# ZMBo_Main.net
KiCad netlist of a schematic drawn in Altium Designer
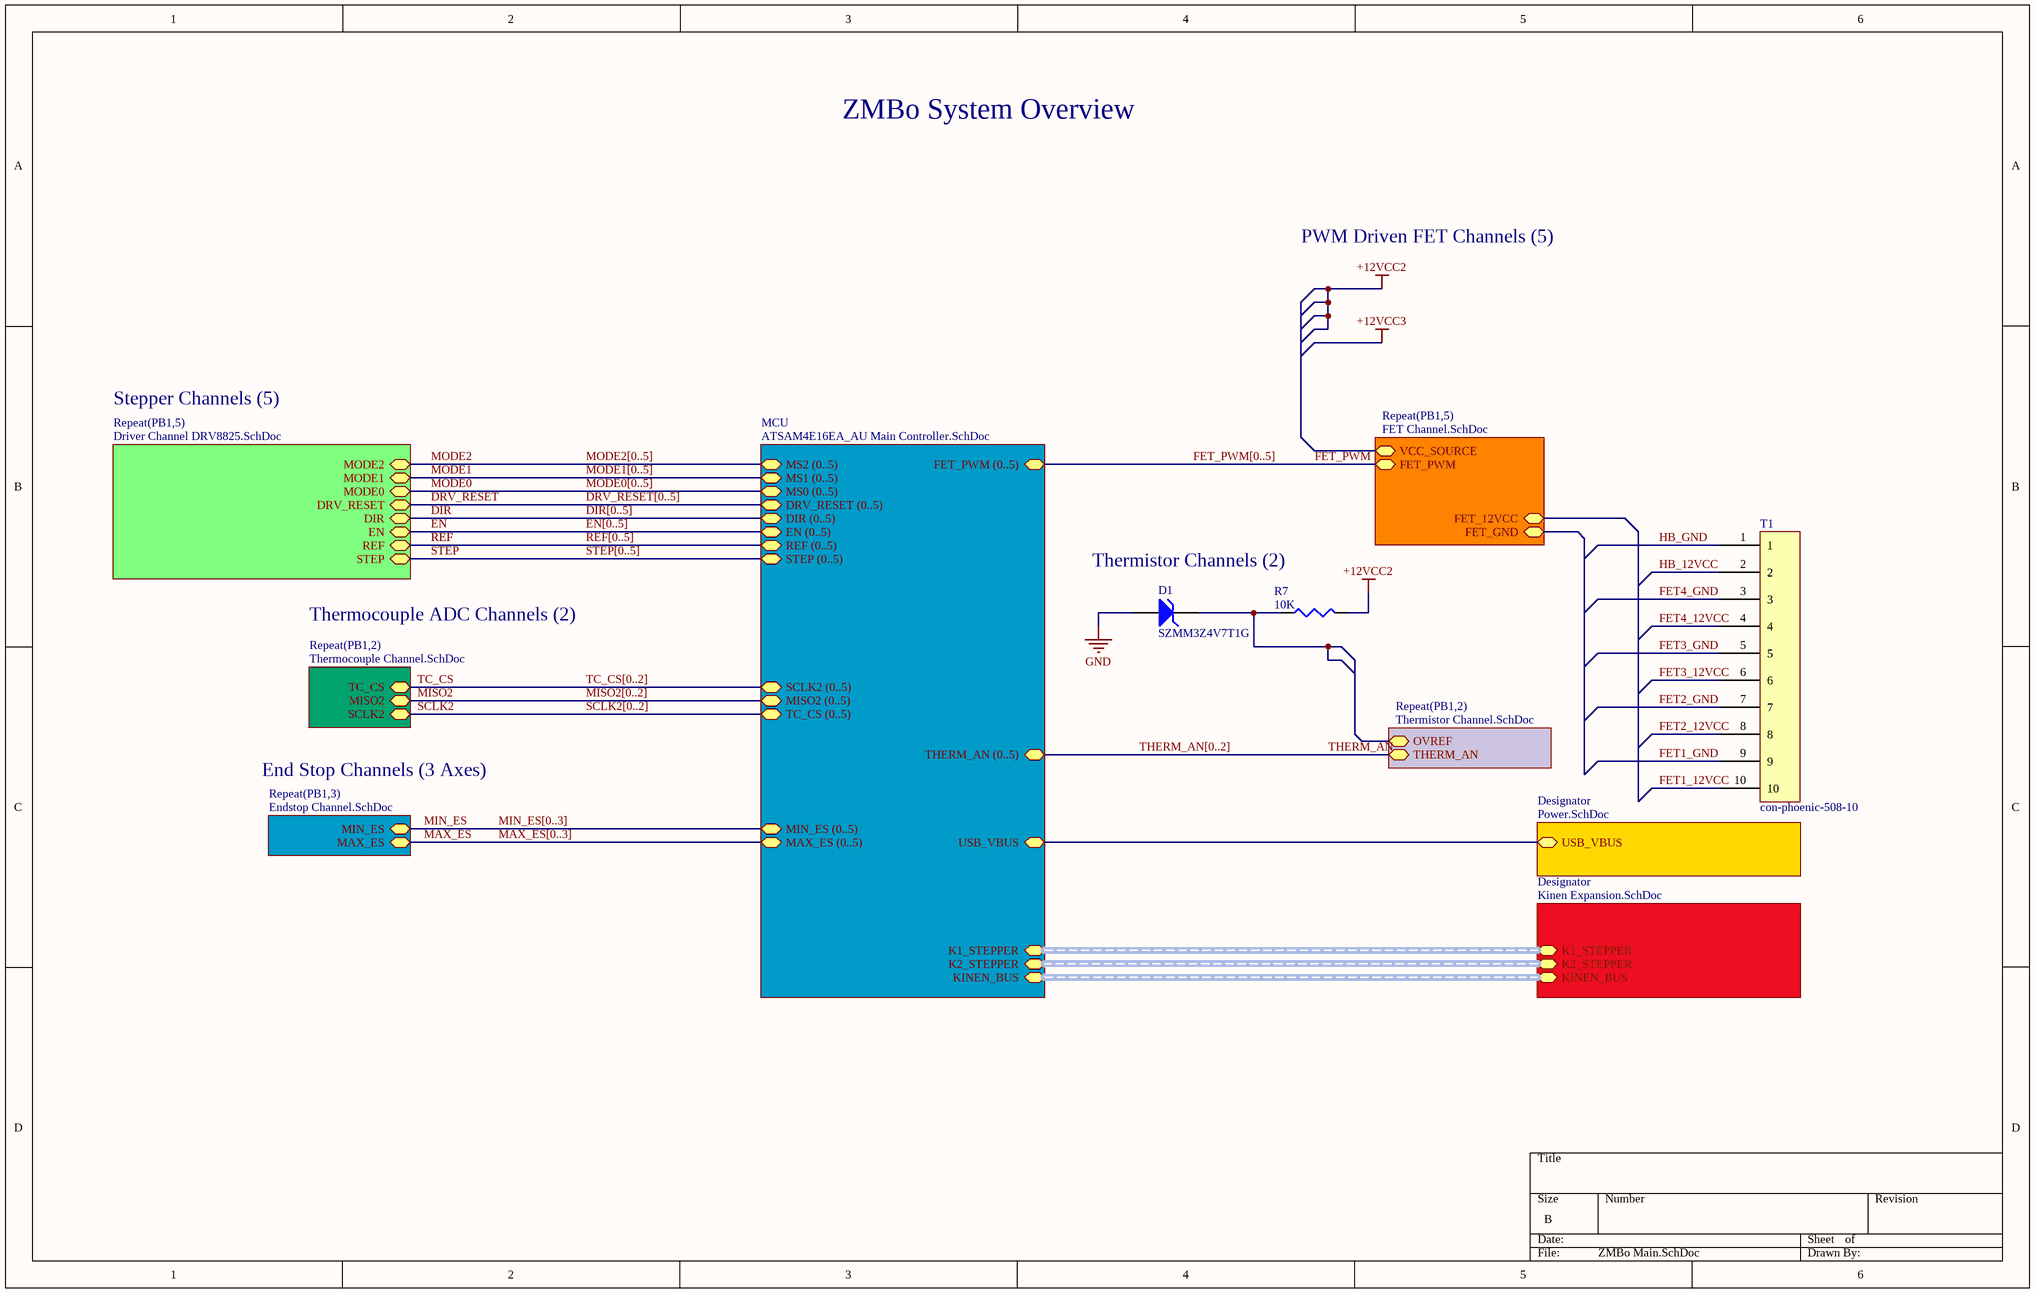
[diagram p0: ZMBo Main.SchDoc]

(export (version "E")
  (design (tool "Eeschema 10.0.6"))
  (components
    (comp (ref "D1")
      (value "SZMM3Z4V7T1G")
      (footprint "SZMM3Z4V7T1G")
      (description "Zener Diode")
      (fields (field (name "PUBLISHER") "Altium Limited"))
      (libsource (lib "Miscellaneous Devices") (part "D Zener"))
    )
    (comp (ref "R7")
      (value "10K")
      (footprint "J1-0603")
      (description "Resistor")
      (fields (field (name "Comment") "Res3") (field (name "PUBLISHER") "Altium Limited"))
      (libsource (lib "Miscellaneous Devices") (part "Res3"))
    )
    (comp (ref "T1")
      (value "con-phoenic-508-10")
      (footprint "con-phoenix-508 - 10")
      (libsource (lib "ZMBo Schematic Library") (part "con-phoenic-508-10"))
    )
  )
  (nets
    (net (code "75") (name "+12VCC2") (class "Default")
      (node (ref "R7") (pin "2") (pinfunction "2_2") (pintype "passive"))
    )
    (net (code "83") (name "/FET1_12VCC") (class "Default")
      (node (ref "T1") (pin "10") (pinfunction "10_10") (pintype "passive"))
    )
    (net (code "84") (name "/FET1_GND") (class "Default")
      (node (ref "T1") (pin "9") (pinfunction "9_9") (pintype "passive"))
    )
    (net (code "85") (name "/FET2_12VCC") (class "Default")
      (node (ref "T1") (pin "8") (pinfunction "8_8") (pintype "passive"))
    )
    (net (code "86") (name "/FET2_GND") (class "Default")
      (node (ref "T1") (pin "7") (pinfunction "7_7") (pintype "passive"))
    )
    (net (code "87") (name "/FET3_12VCC") (class "Default")
      (node (ref "T1") (pin "6") (pinfunction "6_6") (pintype "passive"))
    )
    (net (code "88") (name "/FET3_GND") (class "Default")
      (node (ref "T1") (pin "5") (pinfunction "5_5") (pintype "passive"))
    )
    (net (code "89") (name "/FET4_12VCC") (class "Default")
      (node (ref "T1") (pin "4") (pinfunction "4_4") (pintype "passive"))
    )
    (net (code "90") (name "/FET4_GND") (class "Default")
      (node (ref "T1") (pin "3") (pinfunction "3_3") (pintype "passive"))
    )
    (net (code "95") (name "/HB_12VCC") (class "Default")
      (node (ref "T1") (pin "2") (pinfunction "2_2") (pintype "passive"))
    )
    (net (code "96") (name "/HB_GND") (class "Default")
      (node (ref "T1") (pin "1") (pinfunction "1_1") (pintype "passive"))
    )
    (net (code "125") (name "GND") (class "Default")
      (node (ref "D1") (pin "1") (pinfunction "A_1") (pintype "passive"))
    )
    (net (code "126") (name "Net-(D1-K)") (class "Default")
      (node (ref "D1") (pin "2") (pinfunction "K_2") (pintype "passive"))
      (node (ref "R7") (pin "1") (pinfunction "1_1") (pintype "passive"))
    )
  )
)
